# io-usb.net
KiCad netlist of a schematic drawn in EAGLE
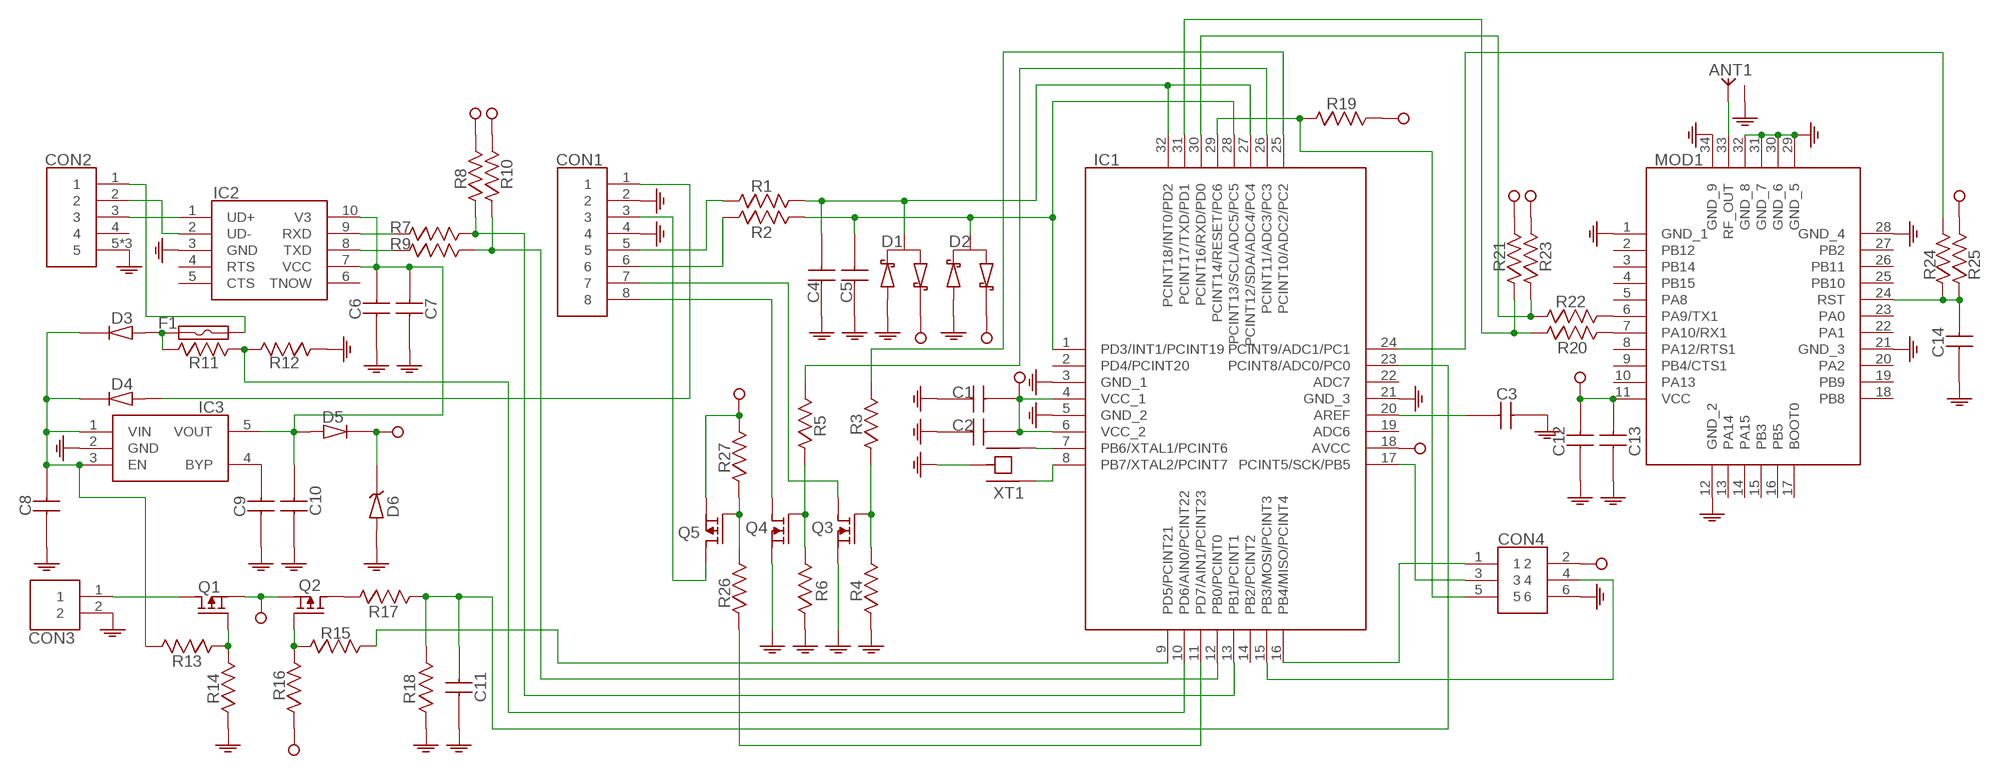
[diagram p0: schematic, sheet 1]

(export (version "E")
  (design (tool "Eeschema 10.0.6"))
  (components
    (comp (ref "ANT1")
      (value "SMA-RF")
      (footprint "eagle-import:SMA-RF")
      (libsource (lib "eagle-import") (part "SMA-RF"))
    )
    (comp (ref "C1")
      (value "CAPACITOR-0805")
      (footprint "eagle-import:0805")
      (libsource (lib "eagle-import") (part "CAPACITOR-0805"))
    )
    (comp (ref "C2")
      (value "CAPACITOR-0603")
      (footprint "eagle-import:0603")
      (libsource (lib "eagle-import") (part "CAPACITOR-0603"))
    )
    (comp (ref "C3")
      (value "CAPACITOR-0603")
      (footprint "eagle-import:0603")
      (libsource (lib "eagle-import") (part "CAPACITOR-0603"))
    )
    (comp (ref "C4")
      (value "CAPACITOR-0603")
      (footprint "eagle-import:0603")
      (libsource (lib "eagle-import") (part "CAPACITOR-0603"))
    )
    (comp (ref "C5")
      (value "CAPACITOR-0603")
      (footprint "eagle-import:0603")
      (libsource (lib "eagle-import") (part "CAPACITOR-0603"))
    )
    (comp (ref "C6")
      (value "CAPACITOR-0805")
      (footprint "eagle-import:0805")
      (libsource (lib "eagle-import") (part "CAPACITOR-0805"))
    )
    (comp (ref "C7")
      (value "CAPACITOR-0603")
      (footprint "eagle-import:0603")
      (libsource (lib "eagle-import") (part "CAPACITOR-0603"))
    )
    (comp (ref "C8")
      (value "CAPACITOR-0805")
      (footprint "eagle-import:0805")
      (libsource (lib "eagle-import") (part "CAPACITOR-0805"))
    )
    (comp (ref "C9")
      (value "CAPACITOR-0603")
      (footprint "eagle-import:0603")
      (libsource (lib "eagle-import") (part "CAPACITOR-0603"))
    )
    (comp (ref "C10")
      (value "CAPACITOR-0805")
      (footprint "eagle-import:0805")
      (libsource (lib "eagle-import") (part "CAPACITOR-0805"))
    )
    (comp (ref "C11")
      (value "CAPACITOR-0603")
      (footprint "eagle-import:0603")
      (libsource (lib "eagle-import") (part "CAPACITOR-0603"))
    )
    (comp (ref "C12")
      (value "CAPACITOR-0603")
      (footprint "eagle-import:0603")
      (libsource (lib "eagle-import") (part "CAPACITOR-0603"))
    )
    (comp (ref "C13")
      (value "CAPACITOR-0805")
      (footprint "eagle-import:0805")
      (libsource (lib "eagle-import") (part "CAPACITOR-0805"))
    )
    (comp (ref "C14")
      (value "CAPACITOR-0603")
      (footprint "eagle-import:0603")
      (libsource (lib "eagle-import") (part "CAPACITOR-0603"))
    )
    (comp (ref "CON1")
      (value "CON-89-3_81-PLUG")
      (footprint "eagle-import:CON-8P-3_81-PLUG")
      (libsource (lib "eagle-import") (part "CON-89-3_81-PLUG"))
    )
    (comp (ref "CON2")
      (value "USB-MICRO-DIP-VER")
      (footprint "eagle-import:USB-MICRO-DIP-VER")
      (libsource (lib "eagle-import") (part "USB-MICRO-DIP-VER"))
    )
    (comp (ref "CON3")
      (value "JST-PH-2-2.0MM")
      (footprint "eagle-import:JST-PH-2-2.0MM")
      (libsource (lib "eagle-import") (part "JST-PH-2-2.0MM"))
    )
    (comp (ref "CON4")
      (value "ISP")
      (footprint "eagle-import:ISP")
      (libsource (lib "eagle-import") (part "ISP"))
    )
    (comp (ref "D1")
      (value "SCHOTTKY-SERIE-3P")
      (footprint "eagle-import:SOT23-3")
      (libsource (lib "eagle-import") (part "SCHOTTKY-SERIE-3P"))
    )
    (comp (ref "D2")
      (value "SCHOTTKY-SERIE-3P")
      (footprint "eagle-import:SOT23-3")
      (libsource (lib "eagle-import") (part "SCHOTTKY-SERIE-3P"))
    )
    (comp (ref "D3")
      (value "DIODE-SOD123")
      (footprint "eagle-import:SOD123-DIODE")
      (libsource (lib "eagle-import") (part "DIODE-SOD123"))
    )
    (comp (ref "D4")
      (value "DIODE-SOD123")
      (footprint "eagle-import:SOD123-DIODE")
      (libsource (lib "eagle-import") (part "DIODE-SOD123"))
    )
    (comp (ref "D5")
      (value "DIODE-SOD123")
      (footprint "eagle-import:SOD123-DIODE")
      (libsource (lib "eagle-import") (part "DIODE-SOD123"))
    )
    (comp (ref "D6")
      (value "ZENER-SOD123")
      (footprint "eagle-import:SOD123-DIODE")
      (libsource (lib "eagle-import") (part "ZENER-SOD123"))
    )
    (comp (ref "F1")
      (value "FUSE-0805")
      (footprint "eagle-import:0805")
      (libsource (lib "eagle-import") (part "FUSE-0805"))
    )
    (comp (ref "IC1")
      (value "ATMEGA328P-AU")
      (footprint "eagle-import:TQFP-32")
      (libsource (lib "eagle-import") (part "ATMEGA328P-AU"))
    )
    (comp (ref "IC2")
      (value "CH340E")
      (footprint "eagle-import:MSOP-10")
      (libsource (lib "eagle-import") (part "CH340E"))
    )
    (comp (ref "IC3")
      (value "MIC5219")
      (footprint "eagle-import:SOT23-5")
      (libsource (lib "eagle-import") (part "MIC5219"))
    )
    (comp (ref "MOD1")
      (value "RAK811")
      (footprint "eagle-import:RAK811")
      (libsource (lib "eagle-import") (part "RAK811"))
    )
    (comp (ref "Q1")
      (value "P-MOSFET")
      (footprint "eagle-import:SOT23-3")
      (libsource (lib "eagle-import") (part "P-MOSFET"))
    )
    (comp (ref "Q2")
      (value "P-MOSFET")
      (footprint "eagle-import:SOT23-3")
      (libsource (lib "eagle-import") (part "P-MOSFET"))
    )
    (comp (ref "Q3")
      (value "N-MOSFET")
      (footprint "eagle-import:SOT23-3")
      (libsource (lib "eagle-import") (part "N-MOSFET"))
    )
    (comp (ref "Q4")
      (value "N-MOSFET")
      (footprint "eagle-import:SOT23-3")
      (libsource (lib "eagle-import") (part "N-MOSFET"))
    )
    (comp (ref "Q5")
      (value "P-MOSFET")
      (footprint "eagle-import:SOT23-3")
      (libsource (lib "eagle-import") (part "P-MOSFET"))
    )
    (comp (ref "R1")
      (value "RESISTOR-0805")
      (footprint "eagle-import:0805")
      (libsource (lib "eagle-import") (part "RESISTOR-0805"))
    )
    (comp (ref "R2")
      (value "RESISTOR-0805")
      (footprint "eagle-import:0805")
      (libsource (lib "eagle-import") (part "RESISTOR-0805"))
    )
    (comp (ref "R3")
      (value "RESISTOR-0603")
      (footprint "eagle-import:0603")
      (libsource (lib "eagle-import") (part "RESISTOR-0603"))
    )
    (comp (ref "R4")
      (value "RESISTOR-0603")
      (footprint "eagle-import:0603")
      (libsource (lib "eagle-import") (part "RESISTOR-0603"))
    )
    (comp (ref "R5")
      (value "RESISTOR-0603")
      (footprint "eagle-import:0603")
      (libsource (lib "eagle-import") (part "RESISTOR-0603"))
    )
    (comp (ref "R6")
      (value "RESISTOR-0603")
      (footprint "eagle-import:0603")
      (libsource (lib "eagle-import") (part "RESISTOR-0603"))
    )
    (comp (ref "R7")
      (value "RESISTOR-0603")
      (footprint "eagle-import:0603")
      (libsource (lib "eagle-import") (part "RESISTOR-0603"))
    )
    (comp (ref "R8")
      (value "RESISTOR-0603")
      (footprint "eagle-import:0603")
      (libsource (lib "eagle-import") (part "RESISTOR-0603"))
    )
    (comp (ref "R9")
      (value "RESISTOR-0603")
      (footprint "eagle-import:0603")
      (libsource (lib "eagle-import") (part "RESISTOR-0603"))
    )
    (comp (ref "R10")
      (value "RESISTOR-0603")
      (footprint "eagle-import:0603")
      (libsource (lib "eagle-import") (part "RESISTOR-0603"))
    )
    (comp (ref "R11")
      (value "RESISTOR-0603")
      (footprint "eagle-import:0603")
      (libsource (lib "eagle-import") (part "RESISTOR-0603"))
    )
    (comp (ref "R12")
      (value "RESISTOR-0603")
      (footprint "eagle-import:0603")
      (libsource (lib "eagle-import") (part "RESISTOR-0603"))
    )
    (comp (ref "R13")
      (value "RESISTOR-0603")
      (footprint "eagle-import:0603")
      (libsource (lib "eagle-import") (part "RESISTOR-0603"))
    )
    (comp (ref "R14")
      (value "RESISTOR-0603")
      (footprint "eagle-import:0603")
      (libsource (lib "eagle-import") (part "RESISTOR-0603"))
    )
    (comp (ref "R15")
      (value "RESISTOR-0603")
      (footprint "eagle-import:0603")
      (libsource (lib "eagle-import") (part "RESISTOR-0603"))
    )
    (comp (ref "R16")
      (value "RESISTOR-0603")
      (footprint "eagle-import:0603")
      (libsource (lib "eagle-import") (part "RESISTOR-0603"))
    )
    (comp (ref "R17")
      (value "RESISTOR-0603")
      (footprint "eagle-import:0603")
      (libsource (lib "eagle-import") (part "RESISTOR-0603"))
    )
    (comp (ref "R18")
      (value "RESISTOR-0603")
      (footprint "eagle-import:0603")
      (libsource (lib "eagle-import") (part "RESISTOR-0603"))
    )
    (comp (ref "R19")
      (value "RESISTOR-0603")
      (footprint "eagle-import:0603")
      (libsource (lib "eagle-import") (part "RESISTOR-0603"))
    )
    (comp (ref "R20")
      (value "RESISTOR-0603")
      (footprint "eagle-import:0603")
      (libsource (lib "eagle-import") (part "RESISTOR-0603"))
    )
    (comp (ref "R21")
      (value "RESISTOR-0603")
      (footprint "eagle-import:0603")
      (libsource (lib "eagle-import") (part "RESISTOR-0603"))
    )
    (comp (ref "R22")
      (value "RESISTOR-0603")
      (footprint "eagle-import:0603")
      (libsource (lib "eagle-import") (part "RESISTOR-0603"))
    )
    (comp (ref "R23")
      (value "RESISTOR-0603")
      (footprint "eagle-import:0603")
      (libsource (lib "eagle-import") (part "RESISTOR-0603"))
    )
    (comp (ref "R24")
      (value "RESISTOR-0603")
      (footprint "eagle-import:0603")
      (libsource (lib "eagle-import") (part "RESISTOR-0603"))
    )
    (comp (ref "R25")
      (value "RESISTOR-0603")
      (footprint "eagle-import:0603")
      (libsource (lib "eagle-import") (part "RESISTOR-0603"))
    )
    (comp (ref "R26")
      (value "RESISTOR-0603")
      (footprint "eagle-import:0603")
      (libsource (lib "eagle-import") (part "RESISTOR-0603"))
    )
    (comp (ref "R27")
      (value "RESISTOR-0603")
      (footprint "eagle-import:0603")
      (libsource (lib "eagle-import") (part "RESISTOR-0603"))
    )
    (comp (ref "XT1")
      (value "RESONATOR-3215")
      (footprint "eagle-import:RESONATOR-3215")
      (libsource (lib "eagle-import") (part "RESONATOR-3215"))
    )
  )
  (nets
    (net (code "1") (name "/PD4{slash}PCINT20") (class "Default")
      (node (ref "IC1") (pin "2") (pinfunction "PD4/PCINT20_2") (pintype "power_in"))
    )
    (net (code "2") (name "GND") (class "Default")
      (node (ref "ANT1") (pin "2") (pinfunction "GND_2") (pintype "power_in"))
      (node (ref "ANT1") (pin "3") (pinfunction "GND_3") (pintype "power_in"))
      (node (ref "ANT1") (pin "4") (pinfunction "GND_4") (pintype "power_in"))
      (node (ref "ANT1") (pin "5") (pinfunction "GND_5") (pintype "power_in"))
      (node (ref "C1") (pin "1") (pinfunction "1_1") (pintype "passive"))
      (node (ref "C10") (pin "1") (pinfunction "1_1") (pintype "passive"))
      (node (ref "C11") (pin "1") (pinfunction "1_1") (pintype "passive"))
      (node (ref "C12") (pin "1") (pinfunction "1_1") (pintype "passive"))
      (node (ref "C13") (pin "1") (pinfunction "1_1") (pintype "passive"))
      (node (ref "C14") (pin "1") (pinfunction "1_1") (pintype "passive"))
      (node (ref "C2") (pin "1") (pinfunction "1_1") (pintype "passive"))
      (node (ref "C3") (pin "2") (pinfunction "2_2") (pintype "passive"))
      (node (ref "C4") (pin "1") (pinfunction "1_1") (pintype "passive"))
      (node (ref "C5") (pin "1") (pinfunction "1_1") (pintype "passive"))
      (node (ref "C6") (pin "1") (pinfunction "1_1") (pintype "passive"))
      (node (ref "C7") (pin "1") (pinfunction "1_1") (pintype "passive"))
      (node (ref "C8") (pin "1") (pinfunction "1_1") (pintype "passive"))
      (node (ref "C9") (pin "2") (pinfunction "2_2") (pintype "passive"))
      (node (ref "CON1") (pin "2") (pinfunction "2_2") (pintype "bidirectional"))
      (node (ref "CON1") (pin "4") (pinfunction "4_4") (pintype "bidirectional"))
      (node (ref "CON2") (pin "5") (pinfunction "5_5") (pintype "bidirectional"))
      (node (ref "CON2") (pin "6") (pinfunction "5_6") (pintype "bidirectional"))
      (node (ref "CON2") (pin "7") (pinfunction "5_7") (pintype "bidirectional"))
      (node (ref "CON3") (pin "2") (pinfunction "2_2") (pintype "bidirectional"))
      (node (ref "CON4") (pin "6") (pinfunction "6_6") (pintype "power_in"))
      (node (ref "D1") (pin "1") (pinfunction "1_1") (pintype "bidirectional"))
      (node (ref "D2") (pin "1") (pinfunction "1_1") (pintype "bidirectional"))
      (node (ref "D6") (pin "2") (pinfunction "A_2") (pintype "bidirectional"))
      (node (ref "IC1") (pin "21") (pinfunction "GND_3_21") (pintype "power_in"))
      (node (ref "IC1") (pin "3") (pinfunction "GND_1_3") (pintype "power_in"))
      (node (ref "IC1") (pin "5") (pinfunction "GND_2_5") (pintype "power_in"))
      (node (ref "IC2") (pin "3") (pinfunction "GND_3") (pintype "power_in"))
      (node (ref "IC3") (pin "2") (pinfunction "GND_2") (pintype "power_in"))
      (node (ref "MOD1") (pin "1") (pinfunction "GND_1_1") (pintype "power_in"))
      (node (ref "MOD1") (pin "12") (pinfunction "GND_2_12") (pintype "power_in"))
      (node (ref "MOD1") (pin "21") (pinfunction "GND_3_21") (pintype "power_in"))
      (node (ref "MOD1") (pin "28") (pinfunction "GND_4_28") (pintype "power_in"))
      (node (ref "MOD1") (pin "29") (pinfunction "GND_5_29") (pintype "power_in"))
      (node (ref "MOD1") (pin "30") (pinfunction "GND_6_30") (pintype "power_in"))
      (node (ref "MOD1") (pin "31") (pinfunction "GND_7_31") (pintype "power_in"))
      (node (ref "MOD1") (pin "32") (pinfunction "GND_8_32") (pintype "power_in"))
      (node (ref "MOD1") (pin "34") (pinfunction "GND_9_34") (pintype "power_in"))
      (node (ref "Q3") (pin "2") (pinfunction "S_2") (pintype "bidirectional"))
      (node (ref "Q4") (pin "2") (pinfunction "S_2") (pintype "bidirectional"))
      (node (ref "R12") (pin "1") (pinfunction "1_1") (pintype "passive"))
      (node (ref "R14") (pin "1") (pinfunction "1_1") (pintype "passive"))
      (node (ref "R18") (pin "1") (pinfunction "1_1") (pintype "passive"))
      (node (ref "R4") (pin "1") (pinfunction "1_1") (pintype "passive"))
      (node (ref "R6") (pin "1") (pinfunction "1_1") (pintype "passive"))
      (node (ref "XT1") (pin "3") (pinfunction "3_3") (pintype "power_in"))
    )
    (net (code "3") (name "Net-(ANT1-ANT)") (class "Default")
      (node (ref "ANT1") (pin "1") (pinfunction "ANT_1") (pintype "bidirectional"))
      (node (ref "MOD1") (pin "33") (pinfunction "RF_OUT_33") (pintype "bidirectional"))
    )
    (net (code "4") (name "Net-(CON1-Pad5)") (class "Default")
      (node (ref "CON1") (pin "5") (pinfunction "5_5") (pintype "bidirectional"))
      (node (ref "R1") (pin "1") (pinfunction "1_1") (pintype "passive"))
    )
    (net (code "5") (name "Net-(CON1-Pad6)") (class "Default")
      (node (ref "CON1") (pin "6") (pinfunction "6_6") (pintype "bidirectional"))
      (node (ref "R2") (pin "1") (pinfunction "1_1") (pintype "passive"))
    )
    (net (code "6") (name "Net-(CON2-Pad1)") (class "Default")
      (node (ref "CON2") (pin "1") (pinfunction "1_1") (pintype "bidirectional"))
      (node (ref "F1") (pin "1") (pinfunction "1_1") (pintype "passive"))
    )
    (net (code "7") (name "Net-(D3-A)") (class "Default")
      (node (ref "D3") (pin "2") (pinfunction "A_2") (pintype "bidirectional"))
      (node (ref "F1") (pin "2") (pinfunction "2_2") (pintype "passive"))
      (node (ref "R11") (pin "1") (pinfunction "1_1") (pintype "passive"))
    )
    (net (code "8") (name "Net-(D3-K)") (class "Default")
      (node (ref "C8") (pin "2") (pinfunction "2_2") (pintype "passive"))
      (node (ref "D3") (pin "1") (pinfunction "K_1") (pintype "bidirectional"))
      (node (ref "D4") (pin "1") (pinfunction "K_1") (pintype "bidirectional"))
      (node (ref "IC3") (pin "1") (pinfunction "VIN_1") (pintype "power_in"))
      (node (ref "IC3") (pin "3") (pinfunction "EN_3") (pintype "input"))
      (node (ref "R13") (pin "2") (pinfunction "2_2") (pintype "passive"))
    )
    (net (code "9") (name "Net-(D4-A)") (class "Default")
      (node (ref "CON1") (pin "1") (pinfunction "1_1") (pintype "bidirectional"))
      (node (ref "D4") (pin "2") (pinfunction "A_2") (pintype "bidirectional"))
    )
    (net (code "10") (name "Net-(D5-A)") (class "Default")
      (node (ref "C10") (pin "2") (pinfunction "2_2") (pintype "passive"))
      (node (ref "C6") (pin "2") (pinfunction "2_2") (pintype "passive"))
      (node (ref "C7") (pin "2") (pinfunction "2_2") (pintype "passive"))
      (node (ref "D5") (pin "2") (pinfunction "A_2") (pintype "bidirectional"))
      (node (ref "IC2") (pin "10") (pinfunction "V3_10") (pintype "power_in"))
      (node (ref "IC2") (pin "7") (pinfunction "VCC_7") (pintype "power_in"))
      (node (ref "IC3") (pin "5") (pinfunction "VOUT_5") (pintype "power_in"))
    )
    (net (code "11") (name "Net-(IC1-AREF)") (class "Default")
      (node (ref "C3") (pin "1") (pinfunction "1_1") (pintype "passive"))
      (node (ref "IC1") (pin "20") (pinfunction "AREF_20") (pintype "bidirectional"))
    )
    (net (code "12") (name "Net-(IC1-PB0{slash}PCINT0)") (class "Default")
      (node (ref "IC1") (pin "12") (pinfunction "PB0/PCINT0_12") (pintype "bidirectional"))
      (node (ref "R10") (pin "1") (pinfunction "1_1") (pintype "passive"))
      (node (ref "R9") (pin "2") (pinfunction "2_2") (pintype "passive"))
    )
    (net (code "13") (name "Net-(IC1-PB1{slash}PCINT1)") (class "Default")
      (node (ref "IC1") (pin "13") (pinfunction "PB1/PCINT1_13") (pintype "bidirectional"))
      (node (ref "R7") (pin "2") (pinfunction "2_2") (pintype "passive"))
      (node (ref "R8") (pin "1") (pinfunction "1_1") (pintype "passive"))
    )
    (net (code "14") (name "Net-(IC1-PB3{slash}MOSI{slash}PCINT3)") (class "Default")
      (node (ref "CON4") (pin "4") (pinfunction "4_4") (pintype "bidirectional"))
      (node (ref "IC1") (pin "15") (pinfunction "PB3/MOSI/PCINT3_15") (pintype "bidirectional"))
    )
    (net (code "15") (name "Net-(IC1-PB4{slash}MISO{slash}PCINT4)") (class "Default")
      (node (ref "CON4") (pin "1") (pinfunction "1_1") (pintype "bidirectional"))
      (node (ref "IC1") (pin "16") (pinfunction "PB4/MISO/PCINT4_16") (pintype "bidirectional"))
    )
    (net (code "16") (name "Net-(IC1-PB6{slash}XTAL1{slash}PCINT6)") (class "Default")
      (node (ref "IC1") (pin "7") (pinfunction "PB6/XTAL1/PCINT6_7") (pintype "bidirectional"))
      (node (ref "XT1") (pin "1") (pinfunction "1_1") (pintype "bidirectional"))
    )
    (net (code "17") (name "Net-(IC1-PB7{slash}XTAL2{slash}PCINT7)") (class "Default")
      (node (ref "IC1") (pin "8") (pinfunction "PB7/XTAL2/PCINT7_8") (pintype "bidirectional"))
      (node (ref "XT1") (pin "2") (pinfunction "2_2") (pintype "bidirectional"))
    )
    (net (code "18") (name "Net-(IC1-PCINT5{slash}SCK{slash}PB5)") (class "Default")
      (node (ref "CON4") (pin "3") (pinfunction "3_3") (pintype "bidirectional"))
      (node (ref "IC1") (pin "17") (pinfunction "PCINT5/SCK/PB5_17") (pintype "bidirectional"))
    )
    (net (code "19") (name "Net-(IC1-PCINT8{slash}ADC0{slash}PC0)") (class "Default")
      (node (ref "C11") (pin "2") (pinfunction "2_2") (pintype "passive"))
      (node (ref "IC1") (pin "23") (pinfunction "PCINT8/ADC0/PC0_23") (pintype "bidirectional"))
      (node (ref "R17") (pin "2") (pinfunction "2_2") (pintype "passive"))
      (node (ref "R18") (pin "2") (pinfunction "2_2") (pintype "passive"))
    )
    (net (code "20") (name "Net-(IC1-PCINT9{slash}ADC1{slash}PC1)") (class "Default")
      (node (ref "IC1") (pin "24") (pinfunction "PCINT9/ADC1/PC1_24") (pintype "bidirectional"))
      (node (ref "R24") (pin "2") (pinfunction "2_2") (pintype "passive"))
    )
    (net (code "21") (name "Net-(IC1-PCINT10{slash}ADC2{slash}PC2)") (class "Default")
      (node (ref "IC1") (pin "25") (pinfunction "PCINT10/ADC2/PC2_25") (pintype "bidirectional"))
      (node (ref "R3") (pin "2") (pinfunction "2_2") (pintype "passive"))
    )
    (net (code "22") (name "Net-(IC1-PCINT11{slash}ADC3{slash}PC3)") (class "Default")
      (node (ref "IC1") (pin "26") (pinfunction "PCINT11/ADC3/PC3_26") (pintype "bidirectional"))
      (node (ref "R5") (pin "2") (pinfunction "2_2") (pintype "passive"))
    )
    (net (code "23") (name "Net-(IC1-PCINT12{slash}SDA{slash}ADC4{slash}PC4)") (class "Default")
      (node (ref "C4") (pin "2") (pinfunction "2_2") (pintype "passive"))
      (node (ref "D1") (pin "3") (pinfunction "3_3") (pintype "bidirectional"))
      (node (ref "IC1") (pin "27") (pinfunction "PCINT12/SDA/ADC4/PC4_27") (pintype "bidirectional"))
      (node (ref "IC1") (pin "32") (pinfunction "PCINT18/INT0/PD2_32") (pintype "bidirectional"))
      (node (ref "R1") (pin "2") (pinfunction "2_2") (pintype "passive"))
    )
    (net (code "24") (name "Net-(IC1-PCINT13{slash}SCL{slash}ADC5{slash}PC5)") (class "Default")
      (node (ref "C5") (pin "2") (pinfunction "2_2") (pintype "passive"))
      (node (ref "D2") (pin "3") (pinfunction "3_3") (pintype "bidirectional"))
      (node (ref "IC1") (pin "1") (pinfunction "PD3/INT1/PCINT19_1") (pintype "bidirectional"))
      (node (ref "IC1") (pin "28") (pinfunction "PCINT13/SCL/ADC5/PC5_28") (pintype "bidirectional"))
      (node (ref "R2") (pin "2") (pinfunction "2_2") (pintype "passive"))
    )
    (net (code "25") (name "Net-(IC1-PCINT14{slash}RESET{slash}PC6)") (class "Default")
      (node (ref "CON4") (pin "5") (pinfunction "5_5") (pintype "bidirectional"))
      (node (ref "IC1") (pin "29") (pinfunction "PCINT14/RESET/PC6_29") (pintype "bidirectional"))
      (node (ref "R19") (pin "1") (pinfunction "1_1") (pintype "passive"))
    )
    (net (code "26") (name "Net-(IC1-PCINT16{slash}RXD{slash}PD0)") (class "Default")
      (node (ref "IC1") (pin "30") (pinfunction "PCINT16/RXD/PD0_30") (pintype "bidirectional"))
      (node (ref "R22") (pin "1") (pinfunction "1_1") (pintype "passive"))
      (node (ref "R23") (pin "1") (pinfunction "1_1") (pintype "passive"))
    )
    (net (code "27") (name "Net-(IC1-PCINT17{slash}TXD{slash}PD1)") (class "Default")
      (node (ref "IC1") (pin "31") (pinfunction "PCINT17/TXD/PD1_31") (pintype "bidirectional"))
      (node (ref "R20") (pin "1") (pinfunction "1_1") (pintype "passive"))
      (node (ref "R21") (pin "1") (pinfunction "1_1") (pintype "passive"))
    )
    (net (code "28") (name "Net-(IC1-PD5{slash}PCINT21)") (class "Default")
      (node (ref "IC1") (pin "9") (pinfunction "PD5/PCINT21_9") (pintype "bidirectional"))
      (node (ref "R15") (pin "2") (pinfunction "2_2") (pintype "passive"))
    )
    (net (code "29") (name "Net-(IC1-PD6{slash}AIN0{slash}PCINT22)") (class "Default")
      (node (ref "IC1") (pin "10") (pinfunction "PD6/AIN0/PCINT22_10") (pintype "bidirectional"))
      (node (ref "R11") (pin "2") (pinfunction "2_2") (pintype "passive"))
      (node (ref "R12") (pin "2") (pinfunction "2_2") (pintype "passive"))
    )
    (net (code "30") (name "Net-(IC1-PD7{slash}AIN1{slash}PCINT23)") (class "Default")
      (node (ref "IC1") (pin "11") (pinfunction "PD7/AIN1/PCINT23_11") (pintype "bidirectional"))
      (node (ref "R26") (pin "1") (pinfunction "1_1") (pintype "passive"))
    )
    (net (code "31") (name "Net-(IC2-RXD)") (class "Default")
      (node (ref "IC2") (pin "9") (pinfunction "RXD_9") (pintype "bidirectional"))
      (node (ref "R7") (pin "1") (pinfunction "1_1") (pintype "passive"))
    )
    (net (code "32") (name "Net-(IC2-TXD)") (class "Default")
      (node (ref "IC2") (pin "8") (pinfunction "TXD_8") (pintype "bidirectional"))
      (node (ref "R9") (pin "1") (pinfunction "1_1") (pintype "passive"))
    )
    (net (code "33") (name "Net-(IC2-UD+)") (class "Default")
      (node (ref "CON2") (pin "3") (pinfunction "3_3") (pintype "bidirectional"))
      (node (ref "IC2") (pin "1") (pinfunction "UD+_1") (pintype "power_in"))
    )
    (net (code "34") (name "Net-(IC2-UD-)") (class "Default")
      (node (ref "CON2") (pin "2") (pinfunction "2_2") (pintype "bidirectional"))
      (node (ref "IC2") (pin "2") (pinfunction "UD-_2") (pintype "power_in"))
    )
    (net (code "35") (name "Net-(IC3-BYP)") (class "Default")
      (node (ref "C9") (pin "1") (pinfunction "1_1") (pintype "passive"))
      (node (ref "IC3") (pin "4") (pinfunction "BYP_4") (pintype "output"))
    )
    (net (code "36") (name "Net-(MOD1-PA9{slash}TX1)") (class "Default")
      (node (ref "MOD1") (pin "6") (pinfunction "PA9/TX1_6") (pintype "bidirectional"))
      (node (ref "R22") (pin "2") (pinfunction "2_2") (pintype "passive"))
    )
    (net (code "37") (name "Net-(MOD1-PA10{slash}RX1)") (class "Default")
      (node (ref "MOD1") (pin "7") (pinfunction "PA10/RX1_7") (pintype "bidirectional"))
      (node (ref "R20") (pin "2") (pinfunction "2_2") (pintype "passive"))
    )
    (net (code "38") (name "Net-(MOD1-RST)") (class "Default")
      (node (ref "C14") (pin "2") (pinfunction "2_2") (pintype "passive"))
      (node (ref "MOD1") (pin "24") (pinfunction "RST_24") (pintype "bidirectional"))
      (node (ref "R24") (pin "1") (pinfunction "1_1") (pintype "passive"))
      (node (ref "R25") (pin "1") (pinfunction "1_1") (pintype "passive"))
    )
    (net (code "39") (name "Net-(Q1-D)") (class "Default")
      (node (ref "CON3") (pin "1") (pinfunction "1_1") (pintype "bidirectional"))
      (node (ref "Q1") (pin "3") (pinfunction "D_3") (pintype "bidirectional"))
    )
    (net (code "40") (name "Net-(Q1-G)") (class "Default")
      (node (ref "Q1") (pin "1") (pinfunction "G_1") (pintype "bidirectional"))
      (node (ref "R13") (pin "1") (pinfunction "1_1") (pintype "passive"))
      (node (ref "R14") (pin "2") (pinfunction "2_2") (pintype "passive"))
    )
    (net (code "41") (name "Net-(Q2-D)") (class "Default")
      (node (ref "Q2") (pin "3") (pinfunction "D_3") (pintype "bidirectional"))
      (node (ref "R17") (pin "1") (pinfunction "1_1") (pintype "passive"))
    )
    (net (code "42") (name "Net-(Q2-G)") (class "Default")
      (node (ref "Q2") (pin "1") (pinfunction "G_1") (pintype "bidirectional"))
      (node (ref "R15") (pin "1") (pinfunction "1_1") (pintype "passive"))
      (node (ref "R16") (pin "2") (pinfunction "2_2") (pintype "passive"))
    )
    (net (code "43") (name "Net-(Q3-D)") (class "Default")
      (node (ref "CON1") (pin "7") (pinfunction "7_7") (pintype "bidirectional"))
      (node (ref "Q3") (pin "3") (pinfunction "D_3") (pintype "bidirectional"))
    )
    (net (code "44") (name "Net-(Q3-G)") (class "Default")
      (node (ref "Q3") (pin "1") (pinfunction "G_1") (pintype "bidirectional"))
      (node (ref "R3") (pin "1") (pinfunction "1_1") (pintype "passive"))
      (node (ref "R4") (pin "2") (pinfunction "2_2") (pintype "passive"))
    )
    (net (code "45") (name "Net-(Q4-D)") (class "Default")
      (node (ref "CON1") (pin "8") (pinfunction "8_8") (pintype "bidirectional"))
      (node (ref "Q4") (pin "3") (pinfunction "D_3") (pintype "bidirectional"))
    )
    (net (code "46") (name "Net-(Q4-G)") (class "Default")
      (node (ref "Q4") (pin "1") (pinfunction "G_1") (pintype "bidirectional"))
      (node (ref "R5") (pin "1") (pinfunction "1_1") (pintype "passive"))
      (node (ref "R6") (pin "2") (pinfunction "2_2") (pintype "passive"))
    )
    (net (code "47") (name "Net-(Q5-D)") (class "Default")
      (node (ref "CON1") (pin "3") (pinfunction "3_3") (pintype "bidirectional"))
      (node (ref "Q5") (pin "3") (pinfunction "D_3") (pintype "bidirectional"))
    )
    (net (code "48") (name "Net-(Q5-G)") (class "Default")
      (node (ref "Q5") (pin "1") (pinfunction "G_1") (pintype "bidirectional"))
      (node (ref "R26") (pin "2") (pinfunction "2_2") (pintype "passive"))
      (node (ref "R27") (pin "1") (pinfunction "1_1") (pintype "passive"))
    )
    (net (code "49") (name "VCC") (class "Default")
      (node (ref "C1") (pin "2") (pinfunction "2_2") (pintype "passive"))
      (node (ref "C12") (pin "2") (pinfunction "2_2") (pintype "passive"))
      (node (ref "C13") (pin "2") (pinfunction "2_2") (pintype "passive"))
      (node (ref "C2") (pin "2") (pinfunction "2_2") (pintype "passive"))
      (node (ref "CON4") (pin "2") (pinfunction "2_2") (pintype "power_in"))
      (node (ref "D1") (pin "2") (pinfunction "2_2") (pintype "bidirectional"))
      (node (ref "D2") (pin "2") (pinfunction "2_2") (pintype "bidirectional"))
      (node (ref "D5") (pin "1") (pinfunction "K_1") (pintype "bidirectional"))
      (node (ref "D6") (pin "1") (pinfunction "K_1") (pintype "bidirectional"))
      (node (ref "IC1") (pin "18") (pinfunction "AVCC_18") (pintype "power_in"))
      (node (ref "IC1") (pin "4") (pinfunction "VCC_1_4") (pintype "power_in"))
      (node (ref "IC1") (pin "6") (pinfunction "VCC_2_6") (pintype "power_in"))
      (node (ref "MOD1") (pin "11") (pinfunction "VCC_11") (pintype "power_in"))
      (node (ref "Q1") (pin "2") (pinfunction "S_2") (pintype "bidirectional"))
      (node (ref "Q2") (pin "2") (pinfunction "S_2") (pintype "bidirectional"))
      (node (ref "Q5") (pin "2") (pinfunction "S_2") (pintype "bidirectional"))
      (node (ref "R10") (pin "2") (pinfunction "2_2") (pintype "passive"))
      (node (ref "R16") (pin "1") (pinfunction "1_1") (pintype "passive"))
      (node (ref "R19") (pin "2") (pinfunction "2_2") (pintype "passive"))
      (node (ref "R21") (pin "2") (pinfunction "2_2") (pintype "passive"))
      (node (ref "R23") (pin "2") (pinfunction "2_2") (pintype "passive"))
      (node (ref "R25") (pin "2") (pinfunction "2_2") (pintype "passive"))
      (node (ref "R27") (pin "2") (pinfunction "2_2") (pintype "passive"))
      (node (ref "R8") (pin "2") (pinfunction "2_2") (pintype "passive"))
    )
    (net (code "50") (name "unconnected-(CON2-Pad4)") (class "Default")
      (node (ref "CON2") (pin "4") (pinfunction "4_4") (pintype "bidirectional"))
    )
    (net (code "51") (name "unconnected-(IC1-ADC6-Pad19)") (class "Default")
      (node (ref "IC1") (pin "19") (pinfunction "ADC6_19") (pintype "bidirectional"))
    )
    (net (code "52") (name "unconnected-(IC1-ADC7-Pad22)") (class "Default")
      (node (ref "IC1") (pin "22") (pinfunction "ADC7_22") (pintype "bidirectional"))
    )
    (net (code "53") (name "unconnected-(IC1-PB2{slash}PCINT2-Pad14)") (class "Default")
      (node (ref "IC1") (pin "14") (pinfunction "PB2/PCINT2_14") (pintype "bidirectional"))
    )
    (net (code "54") (name "unconnected-(IC2-CTS-Pad5)") (class "Default")
      (node (ref "IC2") (pin "5") (pinfunction "CTS_5") (pintype "bidirectional"))
    )
    (net (code "55") (name "unconnected-(IC2-RTS-Pad4)") (class "Default")
      (node (ref "IC2") (pin "4") (pinfunction "RTS_4") (pintype "bidirectional"))
    )
    (net (code "56") (name "unconnected-(IC2-TNOW-Pad6)") (class "Default")
      (node (ref "IC2") (pin "6") (pinfunction "TNOW_6") (pintype "bidirectional"))
    )
    (net (code "57") (name "unconnected-(MOD1-BOOT0-Pad17)") (class "Default")
      (node (ref "MOD1") (pin "17") (pinfunction "BOOT0_17") (pintype "bidirectional"))
    )
    (net (code "58") (name "unconnected-(MOD1-PA0-Pad23)") (class "Default")
      (node (ref "MOD1") (pin "23") (pinfunction "PA0_23") (pintype "bidirectional"))
    )
    (net (code "59") (name "unconnected-(MOD1-PA1-Pad22)") (class "Default")
      (node (ref "MOD1") (pin "22") (pinfunction "PA1_22") (pintype "bidirectional"))
    )
    (net (code "60") (name "unconnected-(MOD1-PA2-Pad20)") (class "Default")
      (node (ref "MOD1") (pin "20") (pinfunction "PA2_20") (pintype "bidirectional"))
    )
    (net (code "61") (name "unconnected-(MOD1-PA8-Pad5)") (class "Default")
      (node (ref "MOD1") (pin "5") (pinfunction "PA8_5") (pintype "bidirectional"))
    )
    (net (code "62") (name "unconnected-(MOD1-PA12{slash}RTS1-Pad8)") (class "Default")
      (node (ref "MOD1") (pin "8") (pinfunction "PA12/RTS1_8") (pintype "bidirectional"))
    )
    (net (code "63") (name "unconnected-(MOD1-PA13-Pad10)") (class "Default")
      (node (ref "MOD1") (pin "10") (pinfunction "PA13_10") (pintype "bidirectional"))
    )
    (net (code "64") (name "unconnected-(MOD1-PA14-Pad13)") (class "Default")
      (node (ref "MOD1") (pin "13") (pinfunction "PA14_13") (pintype "bidirectional"))
    )
    (net (code "65") (name "unconnected-(MOD1-PA15-Pad14)") (class "Default")
      (node (ref "MOD1") (pin "14") (pinfunction "PA15_14") (pintype "bidirectional"))
    )
    (net (code "66") (name "unconnected-(MOD1-PB2-Pad27)") (class "Default")
      (node (ref "MOD1") (pin "27") (pinfunction "PB2_27") (pintype "bidirectional"))
    )
    (net (code "67") (name "unconnected-(MOD1-PB3-Pad15)") (class "Default")
      (node (ref "MOD1") (pin "15") (pinfunction "PB3_15") (pintype "bidirectional"))
    )
    (net (code "68") (name "unconnected-(MOD1-PB4{slash}CTS1-Pad9)") (class "Default")
      (node (ref "MOD1") (pin "9") (pinfunction "PB4/CTS1_9") (pintype "bidirectional"))
    )
    (net (code "69") (name "unconnected-(MOD1-PB5-Pad16)") (class "Default")
      (node (ref "MOD1") (pin "16") (pinfunction "PB5_16") (pintype "bidirectional"))
    )
    (net (code "70") (name "unconnected-(MOD1-PB8-Pad18)") (class "Default")
      (node (ref "MOD1") (pin "18") (pinfunction "PB8_18") (pintype "bidirectional"))
    )
    (net (code "71") (name "unconnected-(MOD1-PB9-Pad19)") (class "Default")
      (node (ref "MOD1") (pin "19") (pinfunction "PB9_19") (pintype "bidirectional"))
    )
    (net (code "72") (name "unconnected-(MOD1-PB10-Pad25)") (class "Default")
      (node (ref "MOD1") (pin "25") (pinfunction "PB10_25") (pintype "bidirectional"))
    )
    (net (code "73") (name "unconnected-(MOD1-PB11-Pad26)") (class "Default")
      (node (ref "MOD1") (pin "26") (pinfunction "PB11_26") (pintype "bidirectional"))
    )
    (net (code "74") (name "unconnected-(MOD1-PB12-Pad2)") (class "Default")
      (node (ref "MOD1") (pin "2") (pinfunction "PB12_2") (pintype "bidirectional"))
    )
    (net (code "75") (name "unconnected-(MOD1-PB14-Pad3)") (class "Default")
      (node (ref "MOD1") (pin "3") (pinfunction "PB14_3") (pintype "bidirectional"))
    )
    (net (code "76") (name "unconnected-(MOD1-PB15-Pad4)") (class "Default")
      (node (ref "MOD1") (pin "4") (pinfunction "PB15_4") (pintype "bidirectional"))
    )
  )
)
